# 4-POWER.net
KiCad netlist of a schematic drawn in Altium Designer
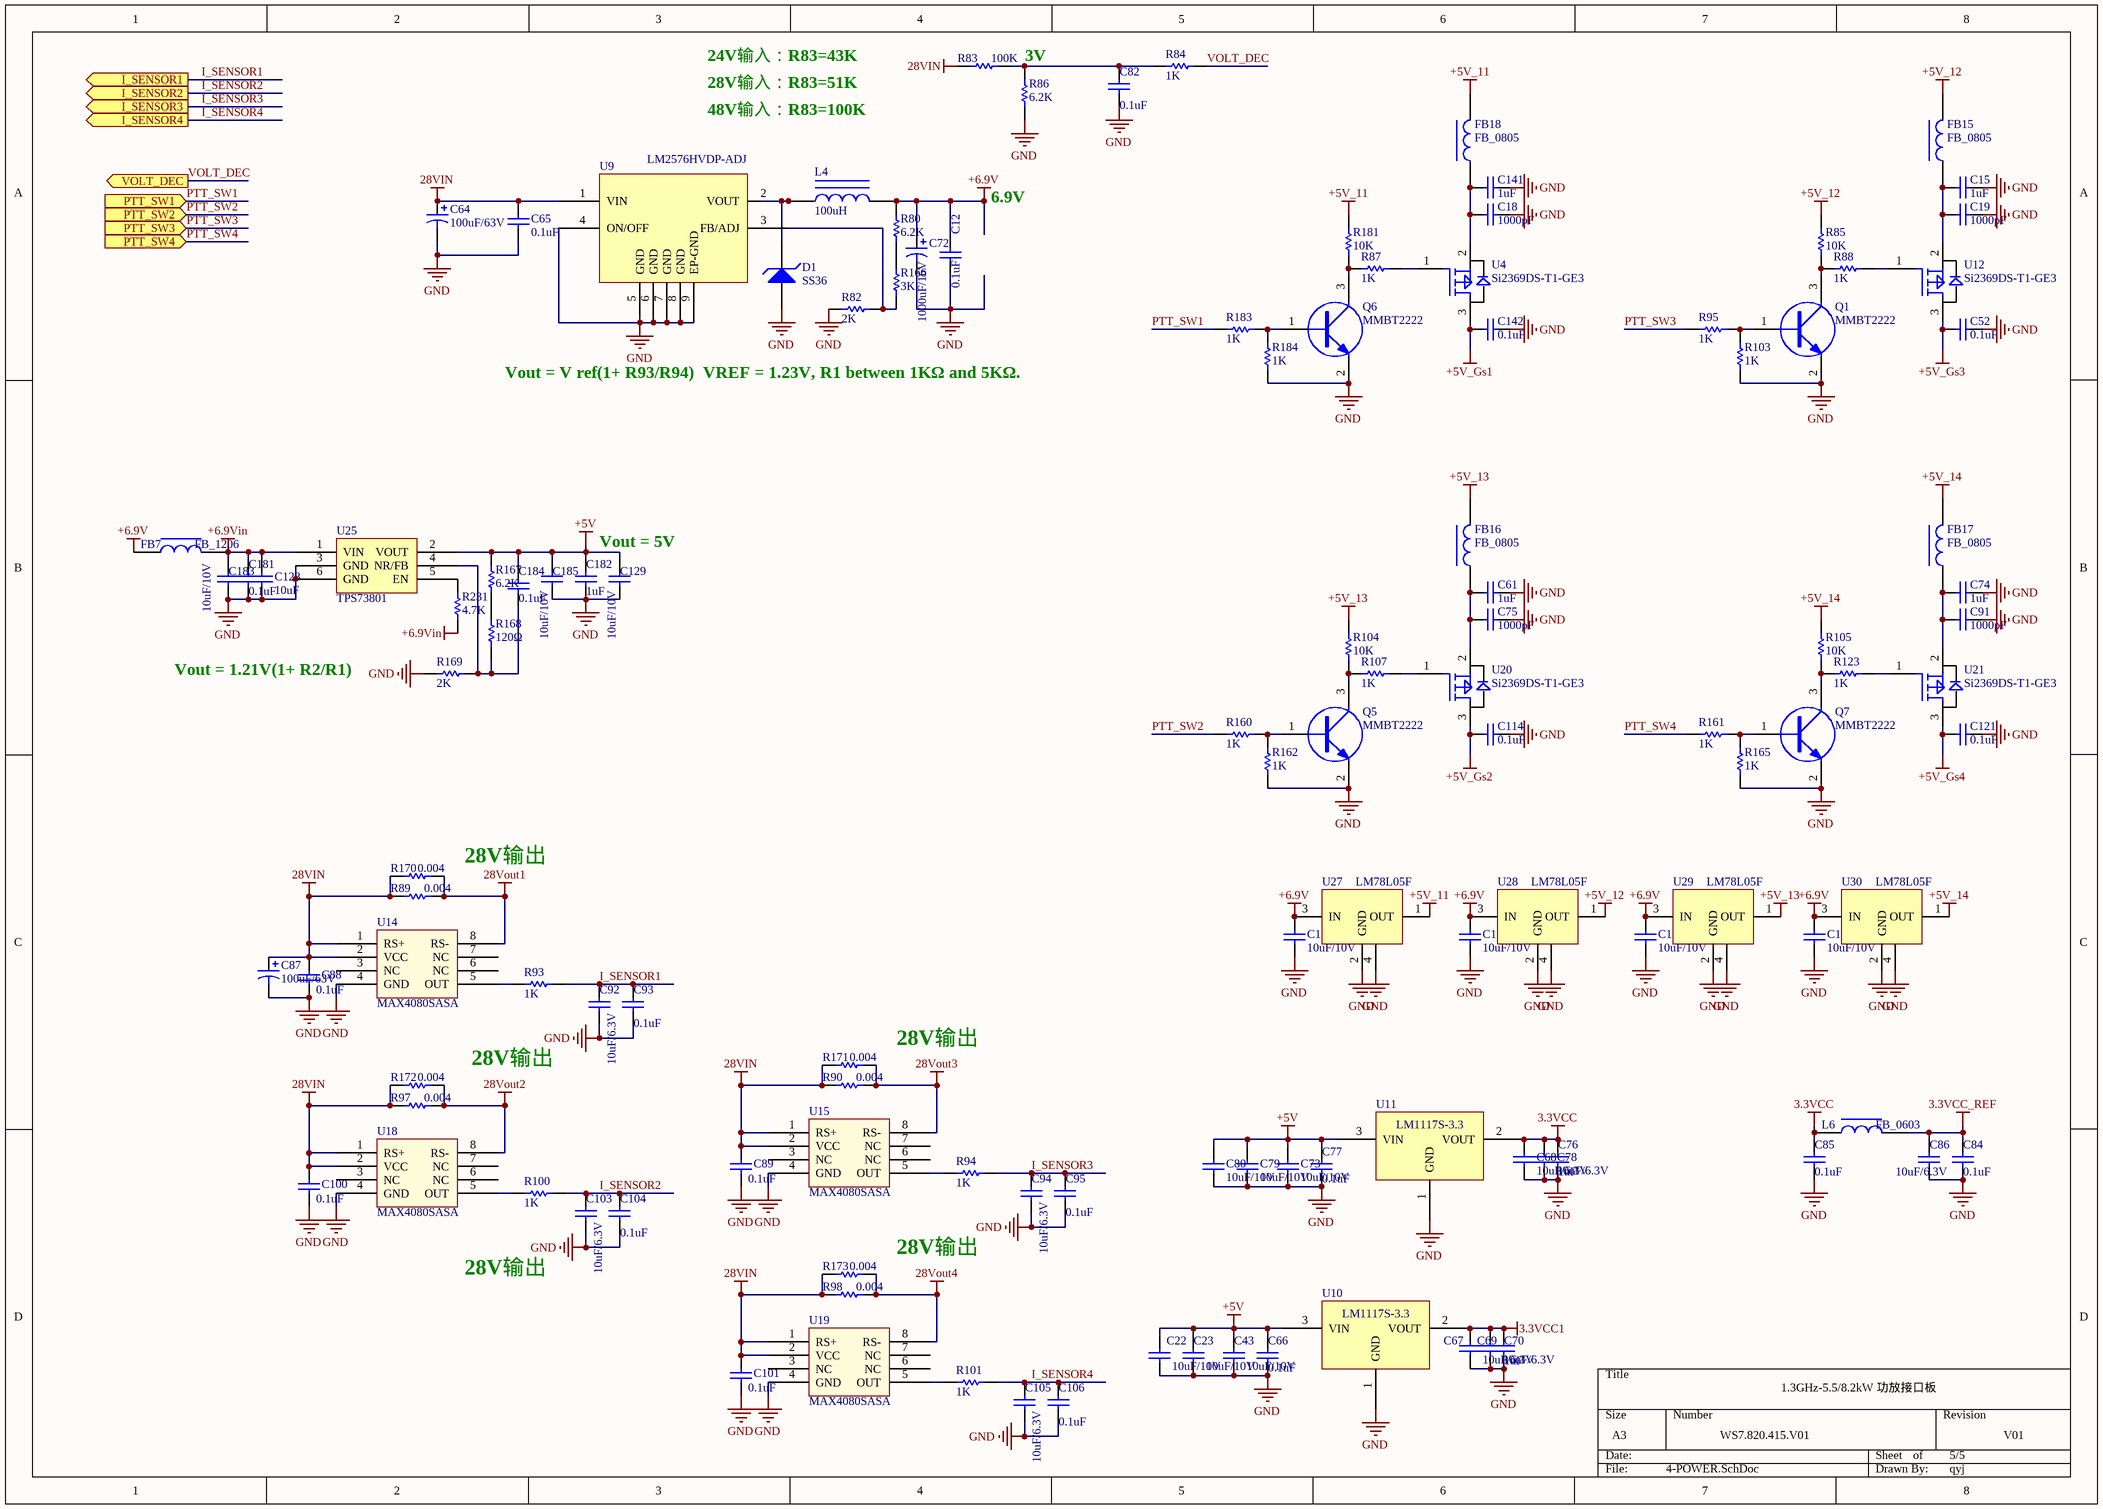
[diagram p0: 4-POWER.SchDoc]

(export (version "E")
  (design (tool "Eeschema 10.0.6"))
  (components
    (comp (ref "C12")
      (value "0.1uF")
      (footprint "C0603")
      (description "贴片电容_GRM188R71H104KA01D_0.1uF±10%,50V,0603")
      (libsource (lib "20贴片电容0603") (part "0.1uF贴片电容"))
    )
    (comp (ref "C15")
      (value "1uF")
      (footprint "C0603")
      (description "贴片电容_GRM188R61A105KA61D_1uF±10%,10V,0603")
      (libsource (lib "20贴片电容0603") (part "1uF贴片电容"))
    )
    (comp (ref "C18")
      (value "1000pF")
      (footprint "C0603")
      (description "贴片电容_GRM188R71H102KA01_1000pF±10%,50V,0603")
      (libsource (lib "20贴片电容0603") (part "1000pF贴片电容"))
    )
    (comp (ref "C19")
      (value "1000pF")
      (footprint "C0603")
      (description "贴片电容_GRM188R71H102KA01_1000pF±10%,50V,0603")
      (libsource (lib "20贴片电容0603") (part "1000pF贴片电容"))
    )
    (comp (ref "C22")
      (value "10uF/10V")
      (footprint "C0805")
      (description "贴片电容_GRM21BR61A106KE19L_10uF±10%,10V,0805")
      (libsource (lib "21贴片电容0805") (part "10uF贴片电容"))
    )
    (comp (ref "C23")
      (value "10uF/10V")
      (footprint "C0805")
      (description "贴片电容_GRM21BR61A106KE19L_10uF±10%,10V,0805")
      (libsource (lib "21贴片电容0805") (part "10uF贴片电容"))
    )
    (comp (ref "C43")
      (value "10uF/10V")
      (footprint "C0805")
      (description "贴片电容_GRM21BR61A106KE19L_10uF±10%,10V,0805")
      (libsource (lib "21贴片电容0805") (part "10uF贴片电容"))
    )
    (comp (ref "C52")
      (value "0.1uF")
      (footprint "C0603")
      (description "贴片电容_GRM188R71H104KA01D_0.1uF±10%,50V,0603")
      (libsource (lib "20贴片电容0603") (part "0.1uF贴片电容"))
    )
    (comp (ref "C61")
      (value "1uF")
      (footprint "C0603")
      (description "贴片电容_GRM188R61A105KA61D_1uF±10%,10V,0603")
      (libsource (lib "20贴片电容0603") (part "1uF贴片电容"))
    )
    (comp (ref "C64")
      (value "100uF/63V")
      (footprint "ECAP2SM_10R4x10R4")
      (description "贴片电解电容_VEJ101M1JTR-1010_100uF/63V,±20%,表贴D10*H10")
      (libsource (lib "24电解电容") (part "100uF/63V"))
    )
    (comp (ref "C65")
      (value "0.1uF")
      (footprint "C0603")
      (description "贴片电容_GRM188R71H104KA01D_0.1uF±10%,50V,0603")
      (libsource (lib "20贴片电容0603") (part "0.1uF贴片电容"))
    )
    (comp (ref "C66")
      (value "0.1uF")
      (footprint "C0603")
      (description "贴片电容_GRM188R71H104KA01D_0.1uF±10%,50V,0603")
      (libsource (lib "20贴片电容0603") (part "0.1uF贴片电容"))
    )
    (comp (ref "C67")
      (value "10uF/6.3V")
      (footprint "C0603")
      (description "贴片电容_GRM188R60J106ME47D_10uF±20%,6.3V,0603")
      (libsource (lib "20贴片电容0603") (part "10uF贴片电容"))
    )
    (comp (ref "C68")
      (value "10uF/6.3V")
      (footprint "C0603")
      (description "贴片电容_GRM188R60J106ME47D_10uF±20%,6.3V,0603")
      (libsource (lib "20贴片电容0603") (part "10uF贴片电容"))
    )
    (comp (ref "C69")
      (value "10uF/6.3V")
      (footprint "C0603")
      (description "贴片电容_GRM188R60J106ME47D_10uF±20%,6.3V,0603")
      (libsource (lib "20贴片电容0603") (part "10uF贴片电容"))
    )
    (comp (ref "C70")
      (value "1uF")
      (footprint "C0603")
      (description "贴片电容_GRM188R61A105KA61D_1uF±10%,10V,0603")
      (libsource (lib "20贴片电容0603") (part "1uF贴片电容"))
    )
    (comp (ref "C72")
      (value "1000uF/16V")
      (footprint "ECAP2SM_10R4x10R4")
      (description "贴片电解电容_VE102M1CTR-1010_1000uF/16V,±20%,表贴10*10")
      (libsource (lib "24电解电容") (part "1000uF/16V"))
    )
    (comp (ref "C73")
      (value "10uF/10V")
      (footprint "C0805")
      (description "贴片电容_GRM21BR61A106KE19L_10uF±10%,10V,0805")
      (libsource (lib "21贴片电容0805") (part "10uF贴片电容"))
    )
    (comp (ref "C74")
      (value "1uF")
      (footprint "C0603")
      (description "贴片电容_GRM188R61A105KA61D_1uF±10%,10V,0603")
      (libsource (lib "20贴片电容0603") (part "1uF贴片电容"))
    )
    (comp (ref "C75")
      (value "1000pF")
      (footprint "C0603")
      (description "贴片电容_GRM188R71H102KA01_1000pF±10%,50V,0603")
      (libsource (lib "20贴片电容0603") (part "1000pF贴片电容"))
    )
    (comp (ref "C76")
      (value "1uF")
      (footprint "C0603")
      (description "贴片电容_GRM188R61A105KA61D_1uF±10%,10V,0603")
      (libsource (lib "20贴片电容0603") (part "1uF贴片电容"))
    )
    (comp (ref "C77")
      (value "0.1uF")
      (footprint "C0603")
      (description "贴片电容_GRM188R71H104KA01D_0.1uF±10%,50V,0603")
      (libsource (lib "20贴片电容0603") (part "0.1uF贴片电容"))
    )
    (comp (ref "C78")
      (value "10uF/6.3V")
      (footprint "C0603")
      (description "贴片电容_GRM188R60J106ME47D_10uF±20%,6.3V,0603")
      (libsource (lib "20贴片电容0603") (part "10uF贴片电容"))
    )
    (comp (ref "C79")
      (value "10uF/10V")
      (footprint "C0805")
      (description "贴片电容_GRM21BR61A106KE19L_10uF±10%,10V,0805")
      (libsource (lib "21贴片电容0805") (part "10uF贴片电容"))
    )
    (comp (ref "C80")
      (value "10uF/10V")
      (footprint "C0805")
      (description "贴片电容_GRM21BR61A106KE19L_10uF±10%,10V,0805")
      (libsource (lib "21贴片电容0805") (part "10uF贴片电容"))
    )
    (comp (ref "C82")
      (value "0.1uF")
      (footprint "C0603")
      (description "贴片电容_GRM188R71H104KA01D_0.1uF±10%,50V,0603")
      (libsource (lib "20贴片电容0603") (part "0.1uF贴片电容"))
    )
    (comp (ref "C84")
      (value "0.1uF")
      (footprint "C0603")
      (description "贴片电容_GRM188R71H104KA01D_0.1uF±10%,50V,0603")
      (libsource (lib "20贴片电容0603") (part "0.1uF贴片电容"))
    )
    (comp (ref "C85")
      (value "0.1uF")
      (footprint "C0603")
      (description "贴片电容_GRM188R71H104KA01D_0.1uF±10%,50V,0603")
      (libsource (lib "20贴片电容0603") (part "0.1uF贴片电容"))
    )
    (comp (ref "C86")
      (value "10uF/6.3V")
      (footprint "C0603")
      (description "贴片电容_GRM188R60J106ME47D_10uF±20%,6.3V,0603")
      (libsource (lib "20贴片电容0603") (part "10uF贴片电容"))
    )
    (comp (ref "C87")
      (value "100uF/63V")
      (footprint "ECAP2SM_10R4x10R4")
      (description "贴片电解电容_VEJ101M1JTR-1010_100uF/63V,±20%,表贴D10*H10")
      (libsource (lib "24电解电容") (part "100uF/63V"))
    )
    (comp (ref "C88")
      (value "0.1uF")
      (footprint "C0603")
      (description "贴片电容_GRM188R71H104KA01D_0.1uF±10%,50V,0603")
      (libsource (lib "20贴片电容0603") (part "0.1uF贴片电容"))
    )
    (comp (ref "C89")
      (value "0.1uF")
      (footprint "C0603")
      (description "贴片电容_GRM188R71H104KA01D_0.1uF±10%,50V,0603")
      (libsource (lib "20贴片电容0603") (part "0.1uF贴片电容"))
    )
    (comp (ref "C91")
      (value "1000pF")
      (footprint "C0603")
      (description "贴片电容_GRM188R71H102KA01_1000pF±10%,50V,0603")
      (libsource (lib "20贴片电容0603") (part "1000pF贴片电容"))
    )
    (comp (ref "C92")
      (value "10uF/6.3V")
      (footprint "C0603")
      (description "贴片电容_GRM188R60J106ME47D_10uF±20%,6.3V,0603")
      (libsource (lib "20贴片电容0603") (part "10uF贴片电容"))
    )
    (comp (ref "C93")
      (value "0.1uF")
      (footprint "C0603")
      (description "贴片电容_GRM188R71H104KA01D_0.1uF±10%,50V,0603")
      (libsource (lib "20贴片电容0603") (part "0.1uF贴片电容"))
    )
    (comp (ref "C94")
      (value "10uF/6.3V")
      (footprint "C0603")
      (description "贴片电容_GRM188R60J106ME47D_10uF±20%,6.3V,0603")
      (libsource (lib "20贴片电容0603") (part "10uF贴片电容"))
    )
    (comp (ref "C95")
      (value "0.1uF")
      (footprint "C0603")
      (description "贴片电容_GRM188R71H104KA01D_0.1uF±10%,50V,0603")
      (libsource (lib "20贴片电容0603") (part "0.1uF贴片电容"))
    )
    (comp (ref "C100")
      (value "0.1uF")
      (footprint "C0603")
      (description "贴片电容_GRM188R71H104KA01D_0.1uF±10%,50V,0603")
      (libsource (lib "20贴片电容0603") (part "0.1uF贴片电容"))
    )
    (comp (ref "C101")
      (value "0.1uF")
      (footprint "C0603")
      (description "贴片电容_GRM188R71H104KA01D_0.1uF±10%,50V,0603")
      (libsource (lib "20贴片电容0603") (part "0.1uF贴片电容"))
    )
    (comp (ref "C103")
      (value "10uF/6.3V")
      (footprint "C0603")
      (description "贴片电容_GRM188R60J106ME47D_10uF±20%,6.3V,0603")
      (libsource (lib "20贴片电容0603") (part "10uF贴片电容"))
    )
    (comp (ref "C104")
      (value "0.1uF")
      (footprint "C0603")
      (description "贴片电容_GRM188R71H104KA01D_0.1uF±10%,50V,0603")
      (libsource (lib "20贴片电容0603") (part "0.1uF贴片电容"))
    )
    (comp (ref "C105")
      (value "10uF/6.3V")
      (footprint "C0603")
      (description "贴片电容_GRM188R60J106ME47D_10uF±20%,6.3V,0603")
      (libsource (lib "20贴片电容0603") (part "10uF贴片电容"))
    )
    (comp (ref "C106")
      (value "0.1uF")
      (footprint "C0603")
      (description "贴片电容_GRM188R71H104KA01D_0.1uF±10%,50V,0603")
      (libsource (lib "20贴片电容0603") (part "0.1uF贴片电容"))
    )
    (comp (ref "C114")
      (value "0.1uF")
      (footprint "C0603")
      (description "贴片电容_GRM188R71H104KA01D_0.1uF±10%,50V,0603")
      (libsource (lib "20贴片电容0603") (part "0.1uF贴片电容"))
    )
    (comp (ref "C121")
      (value "0.1uF")
      (footprint "C0603")
      (description "贴片电容_GRM188R71H104KA01D_0.1uF±10%,50V,0603")
      (libsource (lib "20贴片电容0603") (part "0.1uF贴片电容"))
    )
    (comp (ref "C128")
      (value "10uF")
      (footprint "C1210")
      (description "贴片电容_GRM32ER71H106KA12L_10uF±10%,50V,1210")
      (libsource (lib "23贴片电容1210") (part "10uF贴片电容"))
    )
    (comp (ref "C129")
      (value "10uF/10V")
      (footprint "C0805")
      (description "贴片电容_GRM21BR61A106KE19L_10uF±10%,10V,0805")
      (libsource (lib "21贴片电容0805") (part "10uF贴片电容"))
    )
    (comp (ref "C132")
      (value "10uF/10V")
      (footprint "C0805")
      (description "贴片电容_GRM21BR61A106KE19L_10uF±10%,10V,0805")
      (libsource (lib "21贴片电容0805") (part "10uF贴片电容"))
    )
    (comp (ref "C133")
      (value "10uF/10V")
      (footprint "C0805")
      (description "贴片电容_GRM21BR61A106KE19L_10uF±10%,10V,0805")
      (libsource (lib "21贴片电容0805") (part "10uF贴片电容"))
    )
    (comp (ref "C134")
      (value "10uF/10V")
      (footprint "C0805")
      (description "贴片电容_GRM21BR61A106KE19L_10uF±10%,10V,0805")
      (libsource (lib "21贴片电容0805") (part "10uF贴片电容"))
    )
    (comp (ref "C135")
      (value "10uF/10V")
      (footprint "C0805")
      (description "贴片电容_GRM21BR61A106KE19L_10uF±10%,10V,0805")
      (libsource (lib "21贴片电容0805") (part "10uF贴片电容"))
    )
    (comp (ref "C141")
      (value "1uF")
      (footprint "C0603")
      (description "贴片电容_GRM188R61A105KA61D_1uF±10%,10V,0603")
      (libsource (lib "20贴片电容0603") (part "1uF贴片电容"))
    )
    (comp (ref "C142")
      (value "0.1uF")
      (footprint "C0603")
      (description "贴片电容_GRM188R71H104KA01D_0.1uF±10%,50V,0603")
      (libsource (lib "20贴片电容0603") (part "0.1uF贴片电容"))
    )
    (comp (ref "C181")
      (value "0.1uF")
      (footprint "C0603")
      (description "贴片电容_GRM188R71H104KA01D_0.1uF±10%,50V,0603")
      (libsource (lib "20贴片电容0603") (part "0.1uF贴片电容"))
    )
    (comp (ref "C182")
      (value "1uF")
      (footprint "C0603")
      (description "贴片电容_GRM188R61A105KA61D_1uF±10%,10V,0603")
      (libsource (lib "20贴片电容0603") (part "1uF贴片电容"))
    )
    (comp (ref "C183")
      (value "10uF/10V")
      (footprint "C0805")
      (description "贴片电容_GRM21BR61A106KE19L_10uF±10%,10V,0805")
      (libsource (lib "21贴片电容0805") (part "10uF贴片电容"))
    )
    (comp (ref "C184")
      (value "0.1uF")
      (footprint "C0603")
      (description "贴片电容_GRM188R71H104KA01D_0.1uF±10%,50V,0603")
      (libsource (lib "20贴片电容0603") (part "0.1uF贴片电容"))
    )
    (comp (ref "C185")
      (value "10uF/10V")
      (footprint "C0805")
      (description "贴片电容_GRM21BR61A106KE19L_10uF±10%,10V,0805")
      (libsource (lib "21贴片电容0805") (part "10uF贴片电容"))
    )
    (comp (ref "D1")
      (value "SS36")
      (footprint "DO-214AC")
      (description "肖特基整流二极管_SS36_封装SMA,3A/60V")
      (libsource (lib "40二极管") (part "肖特基整流二极管_SS36"))
    )
    (comp (ref "FB7")
      (value "FB_1206")
      (footprint "L1206")
      (description "贴片磁珠_30R,6A,1206")
      (libsource (lib "34贴片磁珠1206") (part "1206贴片磁珠"))
    )
    (comp (ref "FB15")
      (value "FB_0805")
      (footprint "L0805")
      (description "贴片磁珠_600R,0805")
      (libsource (lib "33贴片磁珠0805") (part "0805贴片磁珠"))
    )
    (comp (ref "FB16")
      (value "FB_0805")
      (footprint "L0805")
      (description "贴片磁珠_600R,0805")
      (libsource (lib "33贴片磁珠0805") (part "0805贴片磁珠"))
    )
    (comp (ref "FB17")
      (value "FB_0805")
      (footprint "L0805")
      (description "贴片磁珠_600R,0805")
      (libsource (lib "33贴片磁珠0805") (part "0805贴片磁珠"))
    )
    (comp (ref "FB18")
      (value "FB_0805")
      (footprint "L0805")
      (description "贴片磁珠_600R,0805")
      (libsource (lib "33贴片磁珠0805") (part "0805贴片磁珠"))
    )
    (comp (ref "L4")
      (value "100uH")
      (footprint "PL2SM-12R5x12R5")
      (description "贴片功率电感_SLF12575T-101M1R9-PF_100uH±20%,额定电流1.9A,12.5x12.5")
      (libsource (lib "32贴片功率电感") (part "100uH贴片功率电感"))
    )
    (comp (ref "L6")
      (value "FB_0603")
      (footprint "L0603")
      (description "贴片磁珠_100R,0603")
      (libsource (lib "32贴片磁珠0603") (part "0603贴片磁珠"))
    )
    (comp (ref "Q1")
      (value "MMBT2222")
      (footprint "SOT23-3")
      (description "NPN三极管_MMBT2222_表贴SOT23")
      (libsource (lib "50三极管") (part "MMBT2222"))
    )
    (comp (ref "Q5")
      (value "MMBT2222")
      (footprint "SOT23-3")
      (description "NPN三极管_MMBT2222_表贴SOT23")
      (libsource (lib "50三极管") (part "MMBT2222"))
    )
    (comp (ref "Q6")
      (value "MMBT2222")
      (footprint "SOT23-3")
      (description "NPN三极管_MMBT2222_表贴SOT23")
      (libsource (lib "50三极管") (part "MMBT2222"))
    )
    (comp (ref "Q7")
      (value "MMBT2222")
      (footprint "SOT23-3")
      (description "NPN三极管_MMBT2222_表贴SOT23")
      (libsource (lib "50三极管") (part "MMBT2222"))
    )
    (comp (ref "R80")
      (value "6.2K")
      (footprint "R0603")
      (description "贴片电阻_6.2K±5%,0603")
      (libsource (lib "10贴片电阻0603") (part "6.2K贴片电阻"))
    )
    (comp (ref "R82")
      (value "2K")
      (footprint "R0603")
      (description "贴片电阻_2K±5%,0603")
      (libsource (lib "10贴片电阻0603") (part "2K贴片电阻"))
    )
    (comp (ref "R83")
      (value "100K")
      (footprint "R0603")
      (description "贴片电阻_12.4K±1%,0603")
      (libsource (lib "10贴片电阻0603") (part "12.4K贴片电阻"))
    )
    (comp (ref "R84")
      (value "1K")
      (footprint "R0603")
      (description "贴片电阻_1K±5%,0603")
      (libsource (lib "10贴片电阻0603") (part "1K贴片电阻"))
    )
    (comp (ref "R85")
      (value "10K")
      (footprint "R0603")
      (description "贴片电阻_10K±5%,0603")
      (libsource (lib "10贴片电阻0603") (part "10K贴片电阻"))
    )
    (comp (ref "R86")
      (value "6.2K")
      (footprint "R0603")
      (description "贴片电阻_1.5K±5%,0603")
      (libsource (lib "10贴片电阻0603") (part "1.5K贴片电阻"))
    )
    (comp (ref "R87")
      (value "1K")
      (footprint "R0603")
      (description "贴片电阻_1K±5%,0603")
      (libsource (lib "10贴片电阻0603") (part "1K贴片电阻"))
    )
    (comp (ref "R88")
      (value "1K")
      (footprint "R0603")
      (description "贴片电阻_1K±5%,0603")
      (libsource (lib "10贴片电阻0603") (part "1K贴片电阻"))
    )
    (comp (ref "R89")
      (value "0.004")
      (footprint "R2512")
      (description "贴片电阻_LR12DTDSR004_0.004±5%,2W,2512")
      (libsource (lib "15贴片检流电阻") (part "0.004Ω检流电阻-标准封装"))
    )
    (comp (ref "R90")
      (value "0.004")
      (footprint "R2512")
      (description "贴片电阻_LR12DTDSR004_0.004±5%,2W,2512")
      (libsource (lib "15贴片检流电阻") (part "0.004Ω检流电阻-标准封装"))
    )
    (comp (ref "R93")
      (value "1K")
      (footprint "R0603")
      (description "贴片电阻_1K±5%,0603")
      (libsource (lib "10贴片电阻0603") (part "1K贴片电阻"))
    )
    (comp (ref "R94")
      (value "1K")
      (footprint "R0603")
      (description "贴片电阻_1K±5%,0603")
      (libsource (lib "10贴片电阻0603") (part "1K贴片电阻"))
    )
    (comp (ref "R95")
      (value "1K")
      (footprint "R0603")
      (description "贴片电阻_1K±5%,0603")
      (libsource (lib "10贴片电阻0603") (part "1K贴片电阻"))
    )
    (comp (ref "R97")
      (value "0.004")
      (footprint "R2512")
      (description "贴片电阻_LR12DTDSR004_0.004±5%,2W,2512")
      (libsource (lib "15贴片检流电阻") (part "0.004Ω检流电阻-标准封装"))
    )
    (comp (ref "R98")
      (value "0.004")
      (footprint "R2512")
      (description "贴片电阻_LR12DTDSR004_0.004±5%,2W,2512")
      (libsource (lib "15贴片检流电阻") (part "0.004Ω检流电阻-标准封装"))
    )
    (comp (ref "R100")
      (value "1K")
      (footprint "R0603")
      (description "贴片电阻_1K±5%,0603")
      (libsource (lib "10贴片电阻0603") (part "1K贴片电阻"))
    )
    (comp (ref "R101")
      (value "1K")
      (footprint "R0603")
      (description "贴片电阻_1K±5%,0603")
      (libsource (lib "10贴片电阻0603") (part "1K贴片电阻"))
    )
    (comp (ref "R103")
      (value "1K")
      (footprint "R0603")
      (description "贴片电阻_1K±5%,0603")
      (libsource (lib "10贴片电阻0603") (part "1K贴片电阻"))
    )
    (comp (ref "R104")
      (value "10K")
      (footprint "R0603")
      (description "贴片电阻_10K±5%,0603")
      (libsource (lib "10贴片电阻0603") (part "10K贴片电阻"))
    )
    (comp (ref "R105")
      (value "10K")
      (footprint "R0603")
      (description "贴片电阻_10K±5%,0603")
      (libsource (lib "10贴片电阻0603") (part "10K贴片电阻"))
    )
    (comp (ref "R107")
      (value "1K")
      (footprint "R0603")
      (description "贴片电阻_1K±5%,0603")
      (libsource (lib "10贴片电阻0603") (part "1K贴片电阻"))
    )
    (comp (ref "R123")
      (value "1K")
      (footprint "R0603")
      (description "贴片电阻_1K±5%,0603")
      (libsource (lib "10贴片电阻0603") (part "1K贴片电阻"))
    )
    (comp (ref "R160")
      (value "1K")
      (footprint "R0603")
      (description "贴片电阻_1K±5%,0603")
      (libsource (lib "10贴片电阻0603") (part "1K贴片电阻"))
    )
    (comp (ref "R161")
      (value "1K")
      (footprint "R0603")
      (description "贴片电阻_1K±5%,0603")
      (libsource (lib "10贴片电阻0603") (part "1K贴片电阻"))
    )
    (comp (ref "R162")
      (value "1K")
      (footprint "R0603")
      (description "贴片电阻_1K±5%,0603")
      (libsource (lib "10贴片电阻0603") (part "1K贴片电阻"))
    )
    (comp (ref "R165")
      (value "1K")
      (footprint "R0603")
      (description "贴片电阻_1K±5%,0603")
      (libsource (lib "10贴片电阻0603") (part "1K贴片电阻"))
    )
    (comp (ref "R166")
      (value "3K")
      (footprint "R0603")
      (description "贴片电阻_3K±5%,0603")
      (libsource (lib "10贴片电阻0603") (part "3K贴片电阻"))
    )
    (comp (ref "R167")
      (value "6.2K")
      (footprint "R0603")
      (description "贴片电阻_6.2K±5%,0603")
      (libsource (lib "10贴片电阻0603") (part "6.2K贴片电阻"))
    )
    (comp (ref "R168")
      (value "120Ω")
      (footprint "R0603")
      (description "贴片电阻_120Ω±5%,0603")
      (libsource (lib "10贴片电阻0603") (part "120Ω贴片电阻"))
    )
    (comp (ref "R169")
      (value "2K")
      (footprint "R0603")
      (description "贴片电阻_2K±5%,0603")
      (libsource (lib "10贴片电阻0603") (part "2K贴片电阻"))
    )
    (comp (ref "R170")
      (value "0.004")
      (footprint "R2512")
      (description "贴片电阻_LR12DTDSR004_0.004±5%,2W,2512")
      (libsource (lib "15贴片检流电阻") (part "0.004Ω检流电阻-标准封装"))
    )
    (comp (ref "R171")
      (value "0.004")
      (footprint "R2512")
      (description "贴片电阻_LR12DTDSR004_0.004±5%,2W,2512")
      (libsource (lib "15贴片检流电阻") (part "0.004Ω检流电阻-标准封装"))
    )
    (comp (ref "R172")
      (value "0.004")
      (footprint "R2512")
      (description "贴片电阻_LR12DTDSR004_0.004±5%,2W,2512")
      (libsource (lib "15贴片检流电阻") (part "0.004Ω检流电阻-标准封装"))
    )
    (comp (ref "R173")
      (value "0.004")
      (footprint "R2512")
      (description "贴片电阻_LR12DTDSR004_0.004±5%,2W,2512")
      (libsource (lib "15贴片检流电阻") (part "0.004Ω检流电阻-标准封装"))
    )
    (comp (ref "R181")
      (value "10K")
      (footprint "R0603")
      (description "贴片电阻_10K±5%,0603")
      (libsource (lib "10贴片电阻0603") (part "10K贴片电阻"))
    )
    (comp (ref "R183")
      (value "1K")
      (footprint "R0603")
      (description "贴片电阻_1K±5%,0603")
      (libsource (lib "10贴片电阻0603") (part "1K贴片电阻"))
    )
    (comp (ref "R184")
      (value "1K")
      (footprint "R0603")
      (description "贴片电阻_1K±5%,0603")
      (libsource (lib "10贴片电阻0603") (part "1K贴片电阻"))
    )
    (comp (ref "R231")
      (value "4.7K")
      (footprint "R0603")
      (description "贴片电阻_4.7K±5%,0603")
      (libsource (lib "10贴片电阻0603") (part "4.7K贴片电阻"))
    )
    (comp (ref "U4")
      (value "Si2369DS-T1-GE3")
      (footprint "SOT23-3")
      (description "P-MOS_Si2369DS-T1-GE3_SOT23")
      (libsource (lib "51场效应管") (part "Si2369DS-T1-GE3"))
    )
    (comp (ref "U9")
      (value "LM2576HVDP-ADJ")
      (footprint "SOIC8_1R27_3R9x4R9-1")
      (description "稳压集成电路_LM2576HVDP-ADJ_3A输出,SOIC8")
      (libsource (lib "78电源芯片") (part "LM2576HVDP-ADJ"))
    )
    (comp (ref "U10")
      (value "LM1117S-3.3")
      (footprint "SOT-223")
      (description "LDO_LM1117S-3.3_1A输出,SOT223")
      (libsource (lib "78电源芯片") (part "LM1117S-3.3"))
    )
    (comp (ref "U11")
      (value "LM1117S-3.3")
      (footprint "SOT-223")
      (description "LDO_LM1117S-3.3_1A输出,SOT223")
      (libsource (lib "78电源芯片") (part "LM1117S-3.3"))
    )
    (comp (ref "U12")
      (value "Si2369DS-T1-GE3")
      (footprint "SOT23-3")
      (description "P-MOS_Si2369DS-T1-GE3_SOT23")
      (libsource (lib "51场效应管") (part "Si2369DS-T1-GE3"))
    )
    (comp (ref "U14")
      (value "MAX4080SASA")
      (footprint "SOIC8_1R27_3R9x4R9")
      (description "电流检测放大器_MAX4080SASA_SOIC8")
      (libsource (lib "79电流检测芯片") (part "MAX4080TASA"))
    )
    (comp (ref "U15")
      (value "MAX4080SASA")
      (footprint "SOIC8_1R27_3R9x4R9")
      (description "电流检测放大器_MAX4080SASA_SOIC8")
      (libsource (lib "79电流检测芯片") (part "MAX4080TASA"))
    )
    (comp (ref "U18")
      (value "MAX4080SASA")
      (footprint "SOIC8_1R27_3R9x4R9")
      (description "电流检测放大器_MAX4080SASA_SOIC8")
      (libsource (lib "79电流检测芯片") (part "MAX4080TASA"))
    )
    (comp (ref "U19")
      (value "MAX4080SASA")
      (footprint "SOIC8_1R27_3R9x4R9")
      (description "电流检测放大器_MAX4080SASA_SOIC8")
      (libsource (lib "79电流检测芯片") (part "MAX4080TASA"))
    )
    (comp (ref "U20")
      (value "Si2369DS-T1-GE3")
      (footprint "SOT23-3")
      (description "P-MOS_Si2369DS-T1-GE3_SOT23")
      (libsource (lib "51场效应管") (part "Si2369DS-T1-GE3"))
    )
    (comp (ref "U21")
      (value "Si2369DS-T1-GE3")
      (footprint "SOT23-3")
      (description "P-MOS_Si2369DS-T1-GE3_SOT23")
      (libsource (lib "51场效应管") (part "Si2369DS-T1-GE3"))
    )
    (comp (ref "U25")
      (value "TPS73801")
      (footprint "SOT-223-6")
      (description "LDO_TPS73801_1A输出,SOT223-6")
      (libsource (lib "78电源芯片") (part "TPS73701DCQ"))
    )
    (comp (ref "U27")
      (value "LM78L05F")
      (footprint "SOT-89")
      (description "功率放大器_LM78L05F_5V输出,100mA输出,SOT89")
      (libsource (lib "78电源芯片") (part "LM78L05F"))
    )
    (comp (ref "U28")
      (value "LM78L05F")
      (footprint "SOT-89")
      (description "功率放大器_LM78L05F_5V输出,100mA输出,SOT89")
      (libsource (lib "78电源芯片") (part "LM78L05F"))
    )
    (comp (ref "U29")
      (value "LM78L05F")
      (footprint "SOT-89")
      (description "功率放大器_LM78L05F_5V输出,100mA输出,SOT89")
      (libsource (lib "78电源芯片") (part "LM78L05F"))
    )
    (comp (ref "U30")
      (value "LM78L05F")
      (footprint "SOT-89")
      (description "功率放大器_LM78L05F_5V输出,100mA输出,SOT89")
      (libsource (lib "78电源芯片") (part "LM78L05F"))
    )
  )
  (nets
    (net (code "1") (name "+5V") (class "Default")
      (node (ref "C129") (pin "2") (pinfunction "2_2") (pintype "passive"))
      (node (ref "C182") (pin "2") (pinfunction "2_2") (pintype "passive"))
      (node (ref "C184") (pin "2") (pinfunction "2_2") (pintype "passive"))
      (node (ref "C185") (pin "2") (pinfunction "2_2") (pintype "passive"))
      (node (ref "C22") (pin "2") (pinfunction "2_2") (pintype "passive"))
      (node (ref "C23") (pin "2") (pinfunction "2_2") (pintype "passive"))
      (node (ref "C43") (pin "2") (pinfunction "2_2") (pintype "passive"))
      (node (ref "C66") (pin "2") (pinfunction "2_2") (pintype "passive"))
      (node (ref "C73") (pin "2") (pinfunction "2_2") (pintype "passive"))
      (node (ref "C77") (pin "2") (pinfunction "2_2") (pintype "passive"))
      (node (ref "C79") (pin "2") (pinfunction "2_2") (pintype "passive"))
      (node (ref "C80") (pin "2") (pinfunction "2_2") (pintype "passive"))
      (node (ref "R167") (pin "2") (pinfunction "2_2") (pintype "passive"))
      (node (ref "U10") (pin "3") (pinfunction "VIN_3") (pintype "passive"))
      (node (ref "U11") (pin "3") (pinfunction "VIN_3") (pintype "passive"))
      (node (ref "U25") (pin "2") (pinfunction "VOUT_2") (pintype "passive"))
    )
    (net (code "2") (name "+5V_11") (class "Default")
      (node (ref "FB18") (pin "2") (pinfunction "2_2") (pintype "passive"))
      (node (ref "R181") (pin "2") (pinfunction "2_2") (pintype "passive"))
      (node (ref "U27") (pin "1") (pinfunction "OUT_1") (pintype "passive"))
    )
    (net (code "3") (name "+5V_12") (class "Default")
      (node (ref "FB15") (pin "2") (pinfunction "2_2") (pintype "passive"))
      (node (ref "R85") (pin "2") (pinfunction "2_2") (pintype "passive"))
      (node (ref "U28") (pin "1") (pinfunction "OUT_1") (pintype "passive"))
    )
    (net (code "4") (name "+5V_13") (class "Default")
      (node (ref "FB16") (pin "2") (pinfunction "2_2") (pintype "passive"))
      (node (ref "R104") (pin "2") (pinfunction "2_2") (pintype "passive"))
      (node (ref "U29") (pin "1") (pinfunction "OUT_1") (pintype "passive"))
    )
    (net (code "5") (name "+5V_14") (class "Default")
      (node (ref "FB17") (pin "2") (pinfunction "2_2") (pintype "passive"))
      (node (ref "R105") (pin "2") (pinfunction "2_2") (pintype "passive"))
      (node (ref "U30") (pin "1") (pinfunction "OUT_1") (pintype "passive"))
    )
    (net (code "6") (name "+5V_Gs1") (class "Default")
      (node (ref "C142") (pin "2") (pinfunction "2_2") (pintype "passive"))
      (node (ref "U4") (pin "3") (pinfunction "D_3") (pintype "passive"))
    )
    (net (code "7") (name "+5V_Gs2") (class "Default")
      (node (ref "C114") (pin "2") (pinfunction "2_2") (pintype "passive"))
      (node (ref "U20") (pin "3") (pinfunction "D_3") (pintype "passive"))
    )
    (net (code "8") (name "+5V_Gs3") (class "Default")
      (node (ref "C52") (pin "2") (pinfunction "2_2") (pintype "passive"))
      (node (ref "U12") (pin "3") (pinfunction "D_3") (pintype "passive"))
    )
    (net (code "9") (name "+5V_Gs4") (class "Default")
      (node (ref "C121") (pin "2") (pinfunction "2_2") (pintype "passive"))
      (node (ref "U21") (pin "3") (pinfunction "D_3") (pintype "passive"))
    )
    (net (code "10") (name "+6.9V") (class "Default")
      (node (ref "C12") (pin "2") (pinfunction "2_2") (pintype "passive"))
      (node (ref "C132") (pin "2") (pinfunction "2_2") (pintype "passive"))
      (node (ref "C133") (pin "2") (pinfunction "2_2") (pintype "passive"))
      (node (ref "C134") (pin "2") (pinfunction "2_2") (pintype "passive"))
      (node (ref "C135") (pin "2") (pinfunction "2_2") (pintype "passive"))
      (node (ref "C72") (pin "1") (pinfunction "1_1") (pintype "passive"))
      (node (ref "FB7") (pin "1") (pinfunction "1_1") (pintype "passive"))
      (node (ref "L4") (pin "2") (pinfunction "2_2") (pintype "passive"))
      (node (ref "R80") (pin "2") (pinfunction "2_2") (pintype "passive"))
      (node (ref "U27") (pin "3") (pinfunction "IN_3") (pintype "passive"))
      (node (ref "U28") (pin "3") (pinfunction "IN_3") (pintype "passive"))
      (node (ref "U29") (pin "3") (pinfunction "IN_3") (pintype "passive"))
      (node (ref "U30") (pin "3") (pinfunction "IN_3") (pintype "passive"))
    )
    (net (code "11") (name "+6.9Vin") (class "Default")
      (node (ref "C128") (pin "2") (pinfunction "2_2") (pintype "passive"))
      (node (ref "C181") (pin "2") (pinfunction "2_2") (pintype "passive"))
      (node (ref "C183") (pin "2") (pinfunction "2_2") (pintype "passive"))
      (node (ref "FB7") (pin "2") (pinfunction "2_2") (pintype "passive"))
      (node (ref "R231") (pin "2") (pinfunction "2_2") (pintype "passive"))
      (node (ref "U25") (pin "1") (pinfunction "VIN_1") (pintype "passive"))
    )
    (net (code "12") (name "/I_SENSOR1") (class "Default")
      (node (ref "C92") (pin "2") (pinfunction "2_2") (pintype "passive"))
      (node (ref "C93") (pin "2") (pinfunction "2_2") (pintype "passive"))
      (node (ref "R93") (pin "2") (pinfunction "2_2") (pintype "passive"))
    )
    (net (code "13") (name "/I_SENSOR2") (class "Default")
      (node (ref "C103") (pin "2") (pinfunction "2_2") (pintype "passive"))
      (node (ref "C104") (pin "2") (pinfunction "2_2") (pintype "passive"))
      (node (ref "R100") (pin "2") (pinfunction "2_2") (pintype "passive"))
    )
    (net (code "14") (name "/I_SENSOR3") (class "Default")
      (node (ref "C94") (pin "2") (pinfunction "2_2") (pintype "passive"))
      (node (ref "C95") (pin "2") (pinfunction "2_2") (pintype "passive"))
      (node (ref "R94") (pin "2") (pinfunction "2_2") (pintype "passive"))
    )
    (net (code "15") (name "/I_SENSOR4") (class "Default")
      (node (ref "C105") (pin "2") (pinfunction "2_2") (pintype "passive"))
      (node (ref "C106") (pin "2") (pinfunction "2_2") (pintype "passive"))
      (node (ref "R101") (pin "2") (pinfunction "2_2") (pintype "passive"))
    )
    (net (code "16") (name "/PTT_SW1") (class "Default")
      (node (ref "R183") (pin "1") (pinfunction "1_1") (pintype "passive"))
    )
    (net (code "17") (name "/PTT_SW2") (class "Default")
      (node (ref "R160") (pin "1") (pinfunction "1_1") (pintype "passive"))
    )
    (net (code "18") (name "/PTT_SW3") (class "Default")
      (node (ref "R95") (pin "1") (pinfunction "1_1") (pintype "passive"))
    )
    (net (code "19") (name "/PTT_SW4") (class "Default")
      (node (ref "R161") (pin "1") (pinfunction "1_1") (pintype "passive"))
    )
    (net (code "20") (name "/VOLT_DEC") (class "Default")
      (node (ref "R84") (pin "1") (pinfunction "1_1") (pintype "passive"))
    )
    (net (code "21") (name "3.3VCC") (class "Default")
      (node (ref "C68") (pin "2") (pinfunction "2_2") (pintype "passive"))
      (node (ref "C76") (pin "2") (pinfunction "2_2") (pintype "passive"))
      (node (ref "C78") (pin "2") (pinfunction "2_2") (pintype "passive"))
      (node (ref "C85") (pin "2") (pinfunction "2_2") (pintype "passive"))
      (node (ref "L6") (pin "1") (pinfunction "1_1") (pintype "passive"))
      (node (ref "U11") (pin "2") (pinfunction "VOUT_2") (pintype "passive"))
    )
    (net (code "22") (name "3.3VCC1") (class "Default")
      (node (ref "C67") (pin "2") (pinfunction "2_2") (pintype "passive"))
      (node (ref "C69") (pin "2") (pinfunction "2_2") (pintype "passive"))
      (node (ref "C70") (pin "2") (pinfunction "2_2") (pintype "passive"))
      (node (ref "U10") (pin "2") (pinfunction "VOUT_2") (pintype "passive"))
    )
    (net (code "23") (name "3.3VCC_REF") (class "Default")
      (node (ref "C84") (pin "2") (pinfunction "2_2") (pintype "passive"))
      (node (ref "C86") (pin "2") (pinfunction "2_2") (pintype "passive"))
      (node (ref "L6") (pin "2") (pinfunction "2_2") (pintype "passive"))
    )
    (net (code "24") (name "28VIN") (class "Default")
      (node (ref "C100") (pin "2") (pinfunction "2_2") (pintype "passive"))
      (node (ref "C101") (pin "2") (pinfunction "2_2") (pintype "passive"))
      (node (ref "C64") (pin "1") (pinfunction "1_1") (pintype "passive"))
      (node (ref "C65") (pin "2") (pinfunction "2_2") (pintype "passive"))
      (node (ref "C87") (pin "1") (pinfunction "1_1") (pintype "passive"))
      (node (ref "C88") (pin "2") (pinfunction "2_2") (pintype "passive"))
      (node (ref "C89") (pin "2") (pinfunction "2_2") (pintype "passive"))
      (node (ref "R170") (pin "1") (pinfunction "1_1") (pintype "passive"))
      (node (ref "R171") (pin "1") (pinfunction "1_1") (pintype "passive"))
      (node (ref "R172") (pin "1") (pinfunction "1_1") (pintype "passive"))
      (node (ref "R173") (pin "1") (pinfunction "1_1") (pintype "passive"))
      (node (ref "R83") (pin "1") (pinfunction "1_1") (pintype "passive"))
      (node (ref "R89") (pin "1") (pinfunction "1_1") (pintype "passive"))
      (node (ref "R90") (pin "1") (pinfunction "1_1") (pintype "passive"))
      (node (ref "R97") (pin "1") (pinfunction "1_1") (pintype "passive"))
      (node (ref "R98") (pin "1") (pinfunction "1_1") (pintype "passive"))
      (node (ref "U14") (pin "1") (pinfunction "RS+_1") (pintype "passive"))
      (node (ref "U14") (pin "2") (pinfunction "VCC_2") (pintype "passive"))
      (node (ref "U15") (pin "1") (pinfunction "RS+_1") (pintype "passive"))
      (node (ref "U15") (pin "2") (pinfunction "VCC_2") (pintype "passive"))
      (node (ref "U18") (pin "1") (pinfunction "RS+_1") (pintype "passive"))
      (node (ref "U18") (pin "2") (pinfunction "VCC_2") (pintype "passive"))
      (node (ref "U19") (pin "1") (pinfunction "RS+_1") (pintype "passive"))
      (node (ref "U19") (pin "2") (pinfunction "VCC_2") (pintype "passive"))
      (node (ref "U9") (pin "1") (pinfunction "VIN_1") (pintype "passive"))
    )
    (net (code "25") (name "28Vout1") (class "Default")
      (node (ref "R170") (pin "2") (pinfunction "2_2") (pintype "passive"))
      (node (ref "R89") (pin "2") (pinfunction "2_2") (pintype "passive"))
      (node (ref "U14") (pin "8") (pinfunction "RS-_8") (pintype "passive"))
    )
    (net (code "26") (name "28Vout2") (class "Default")
      (node (ref "R172") (pin "2") (pinfunction "2_2") (pintype "passive"))
      (node (ref "R97") (pin "2") (pinfunction "2_2") (pintype "passive"))
      (node (ref "U18") (pin "8") (pinfunction "RS-_8") (pintype "passive"))
    )
    (net (code "27") (name "28Vout3") (class "Default")
      (node (ref "R171") (pin "2") (pinfunction "2_2") (pintype "passive"))
      (node (ref "R90") (pin "2") (pinfunction "2_2") (pintype "passive"))
      (node (ref "U15") (pin "8") (pinfunction "RS-_8") (pintype "passive"))
    )
    (net (code "28") (name "28Vout4") (class "Default")
      (node (ref "R173") (pin "2") (pinfunction "2_2") (pintype "passive"))
      (node (ref "R98") (pin "2") (pinfunction "2_2") (pintype "passive"))
      (node (ref "U19") (pin "8") (pinfunction "RS-_8") (pintype "passive"))
    )
    (net (code "29") (name "GND") (class "Default")
      (node (ref "C100") (pin "1") (pinfunction "1_1") (pintype "passive"))
      (node (ref "C101") (pin "1") (pinfunction "1_1") (pintype "passive"))
      (node (ref "C103") (pin "1") (pinfunction "1_1") (pintype "passive"))
      (node (ref "C104") (pin "1") (pinfunction "1_1") (pintype "passive"))
      (node (ref "C105") (pin "1") (pinfunction "1_1") (pintype "passive"))
      (node (ref "C106") (pin "1") (pinfunction "1_1") (pintype "passive"))
      (node (ref "C114") (pin "1") (pinfunction "1_1") (pintype "passive"))
      (node (ref "C12") (pin "1") (pinfunction "1_1") (pintype "passive"))
      (node (ref "C121") (pin "1") (pinfunction "1_1") (pintype "passive"))
      (node (ref "C128") (pin "1") (pinfunction "1_1") (pintype "passive"))
      (node (ref "C129") (pin "1") (pinfunction "1_1") (pintype "passive"))
      (node (ref "C132") (pin "1") (pinfunction "1_1") (pintype "passive"))
      (node (ref "C133") (pin "1") (pinfunction "1_1") (pintype "passive"))
      (node (ref "C134") (pin "1") (pinfunction "1_1") (pintype "passive"))
      (node (ref "C135") (pin "1") (pinfunction "1_1") (pintype "passive"))
      (node (ref "C141") (pin "1") (pinfunction "1_1") (pintype "passive"))
      (node (ref "C142") (pin "1") (pinfunction "1_1") (pintype "passive"))
      (node (ref "C15") (pin "1") (pinfunction "1_1") (pintype "passive"))
      (node (ref "C18") (pin "2") (pinfunction "2_2") (pintype "passive"))
      (node (ref "C181") (pin "1") (pinfunction "1_1") (pintype "passive"))
      (node (ref "C182") (pin "1") (pinfunction "1_1") (pintype "passive"))
      (node (ref "C183") (pin "1") (pinfunction "1_1") (pintype "passive"))
      (node (ref "C185") (pin "1") (pinfunction "1_1") (pintype "passive"))
      (node (ref "C19") (pin "2") (pinfunction "2_2") (pintype "passive"))
      (node (ref "C22") (pin "1") (pinfunction "1_1") (pintype "passive"))
      (node (ref "C23") (pin "1") (pinfunction "1_1") (pintype "passive"))
      (node (ref "C43") (pin "1") (pinfunction "1_1") (pintype "passive"))
      (node (ref "C52") (pin "1") (pinfunction "1_1") (pintype "passive"))
      (node (ref "C61") (pin "1") (pinfunction "1_1") (pintype "passive"))
      (node (ref "C64") (pin "2") (pinfunction "2_2") (pintype "passive"))
      (node (ref "C65") (pin "1") (pinfunction "1_1") (pintype "passive"))
      (node (ref "C66") (pin "1") (pinfunction "1_1") (pintype "passive"))
      (node (ref "C67") (pin "1") (pinfunction "1_1") (pintype "passive"))
      (node (ref "C68") (pin "1") (pinfunction "1_1") (pintype "passive"))
      (node (ref "C69") (pin "1") (pinfunction "1_1") (pintype "passive"))
      (node (ref "C70") (pin "1") (pinfunction "1_1") (pintype "passive"))
      (node (ref "C72") (pin "2") (pinfunction "2_2") (pintype "passive"))
      (node (ref "C73") (pin "1") (pinfunction "1_1") (pintype "passive"))
      (node (ref "C74") (pin "1") (pinfunction "1_1") (pintype "passive"))
      (node (ref "C75") (pin "2") (pinfunction "2_2") (pintype "passive"))
      (node (ref "C76") (pin "1") (pinfunction "1_1") (pintype "passive"))
      (node (ref "C77") (pin "1") (pinfunction "1_1") (pintype "passive"))
      (node (ref "C78") (pin "1") (pinfunction "1_1") (pintype "passive"))
      (node (ref "C79") (pin "1") (pinfunction "1_1") (pintype "passive"))
      (node (ref "C80") (pin "1") (pinfunction "1_1") (pintype "passive"))
      (node (ref "C82") (pin "1") (pinfunction "1_1") (pintype "passive"))
      (node (ref "C84") (pin "1") (pinfunction "1_1") (pintype "passive"))
      (node (ref "C85") (pin "1") (pinfunction "1_1") (pintype "passive"))
      (node (ref "C86") (pin "1") (pinfunction "1_1") (pintype "passive"))
      (node (ref "C87") (pin "2") (pinfunction "2_2") (pintype "passive"))
      (node (ref "C88") (pin "1") (pinfunction "1_1") (pintype "passive"))
      (node (ref "C89") (pin "1") (pinfunction "1_1") (pintype "passive"))
      (node (ref "C91") (pin "2") (pinfunction "2_2") (pintype "passive"))
      (node (ref "C92") (pin "1") (pinfunction "1_1") (pintype "passive"))
      (node (ref "C93") (pin "1") (pinfunction "1_1") (pintype "passive"))
      (node (ref "C94") (pin "1") (pinfunction "1_1") (pintype "passive"))
      (node (ref "C95") (pin "1") (pinfunction "1_1") (pintype "passive"))
      (node (ref "D1") (pin "1") (pinfunction "A_1") (pintype "passive"))
      (node (ref "Q1") (pin "2") (pinfunction "E_2") (pintype "passive"))
      (node (ref "Q5") (pin "2") (pinfunction "E_2") (pintype "passive"))
      (node (ref "Q6") (pin "2") (pinfunction "E_2") (pintype "passive"))
      (node (ref "Q7") (pin "2") (pinfunction "E_2") (pintype "passive"))
      (node (ref "R103") (pin "1") (pinfunction "1_1") (pintype "passive"))
      (node (ref "R162") (pin "1") (pinfunction "1_1") (pintype "passive"))
      (node (ref "R165") (pin "1") (pinfunction "1_1") (pintype "passive"))
      (node (ref "R169") (pin "2") (pinfunction "2_2") (pintype "passive"))
      (node (ref "R184") (pin "1") (pinfunction "1_1") (pintype "passive"))
      (node (ref "R82") (pin "2") (pinfunction "2_2") (pintype "passive"))
      (node (ref "R86") (pin "1") (pinfunction "1_1") (pintype "passive"))
      (node (ref "U10") (pin "1") (pinfunction "GND_1") (pintype "passive"))
      (node (ref "U11") (pin "1") (pinfunction "GND_1") (pintype "passive"))
      (node (ref "U14") (pin "4") (pinfunction "GND_4") (pintype "passive"))
      (node (ref "U15") (pin "4") (pinfunction "GND_4") (pintype "passive"))
      (node (ref "U18") (pin "4") (pinfunction "GND_4") (pintype "passive"))
      (node (ref "U19") (pin "4") (pinfunction "GND_4") (pintype "passive"))
      (node (ref "U25") (pin "3") (pinfunction "GND_3") (pintype "passive"))
      (node (ref "U25") (pin "6") (pinfunction "GND_6") (pintype "passive"))
      (node (ref "U27") (pin "2") (pinfunction "GND_2") (pintype "passive"))
      (node (ref "U27") (pin "4") (pinfunction "GND_4") (pintype "passive"))
      (node (ref "U28") (pin "2") (pinfunction "GND_2") (pintype "passive"))
      (node (ref "U28") (pin "4") (pinfunction "GND_4") (pintype "passive"))
      (node (ref "U29") (pin "2") (pinfunction "GND_2") (pintype "passive"))
      (node (ref "U29") (pin "4") (pinfunction "GND_4") (pintype "passive"))
      (node (ref "U30") (pin "2") (pinfunction "GND_2") (pintype "passive"))
      (node (ref "U30") (pin "4") (pinfunction "GND_4") (pintype "passive"))
      (node (ref "U9") (pin "4") (pinfunction "ON/OFF_4") (pintype "passive"))
      (node (ref "U9") (pin "5") (pinfunction "GND_5") (pintype "passive"))
      (node (ref "U9") (pin "6") (pinfunction "GND_6") (pintype "passive"))
      (node (ref "U9") (pin "7") (pinfunction "GND_7") (pintype "passive"))
      (node (ref "U9") (pin "8") (pinfunction "GND_8") (pintype "passive"))
      (node (ref "U9") (pin "9") (pinfunction "EP-GND_9") (pintype "passive"))
    )
    (net (code "30") (name "Net-(C82-Pad2)") (class "Default")
      (node (ref "C82") (pin "2") (pinfunction "2_2") (pintype "passive"))
      (node (ref "R83") (pin "2") (pinfunction "2_2") (pintype "passive"))
      (node (ref "R84") (pin "2") (pinfunction "2_2") (pintype "passive"))
      (node (ref "R86") (pin "2") (pinfunction "2_2") (pintype "passive"))
    )
    (net (code "31") (name "Net-(D1-K)") (class "Default")
      (node (ref "D1") (pin "2") (pinfunction "K_2") (pintype "passive"))
      (node (ref "L4") (pin "1") (pinfunction "1_1") (pintype "passive"))
      (node (ref "U9") (pin "2") (pinfunction "VOUT_2") (pintype "passive"))
    )
    (net (code "32") (name "Net-(Q1-B)") (class "Default")
      (node (ref "Q1") (pin "1") (pinfunction "B_1") (pintype "passive"))
      (node (ref "R103") (pin "2") (pinfunction "2_2") (pintype "passive"))
      (node (ref "R95") (pin "2") (pinfunction "2_2") (pintype "passive"))
    )
    (net (code "33") (name "Net-(Q1-C)") (class "Default")
      (node (ref "Q1") (pin "3") (pinfunction "C_3") (pintype "passive"))
      (node (ref "R85") (pin "1") (pinfunction "1_1") (pintype "passive"))
      (node (ref "R88") (pin "1") (pinfunction "1_1") (pintype "passive"))
    )
    (net (code "34") (name "Net-(Q5-B)") (class "Default")
      (node (ref "Q5") (pin "1") (pinfunction "B_1") (pintype "passive"))
      (node (ref "R160") (pin "2") (pinfunction "2_2") (pintype "passive"))
      (node (ref "R162") (pin "2") (pinfunction "2_2") (pintype "passive"))
    )
    (net (code "35") (name "Net-(Q5-C)") (class "Default")
      (node (ref "Q5") (pin "3") (pinfunction "C_3") (pintype "passive"))
      (node (ref "R104") (pin "1") (pinfunction "1_1") (pintype "passive"))
      (node (ref "R107") (pin "1") (pinfunction "1_1") (pintype "passive"))
    )
    (net (code "36") (name "Net-(Q6-B)") (class "Default")
      (node (ref "Q6") (pin "1") (pinfunction "B_1") (pintype "passive"))
      (node (ref "R183") (pin "2") (pinfunction "2_2") (pintype "passive"))
      (node (ref "R184") (pin "2") (pinfunction "2_2") (pintype "passive"))
    )
    (net (code "37") (name "Net-(Q6-C)") (class "Default")
      (node (ref "Q6") (pin "3") (pinfunction "C_3") (pintype "passive"))
      (node (ref "R181") (pin "1") (pinfunction "1_1") (pintype "passive"))
      (node (ref "R87") (pin "1") (pinfunction "1_1") (pintype "passive"))
    )
    (net (code "38") (name "Net-(Q7-B)") (class "Default")
      (node (ref "Q7") (pin "1") (pinfunction "B_1") (pintype "passive"))
      (node (ref "R161") (pin "2") (pinfunction "2_2") (pintype "passive"))
      (node (ref "R165") (pin "2") (pinfunction "2_2") (pintype "passive"))
    )
    (net (code "39") (name "Net-(Q7-C)") (class "Default")
      (node (ref "Q7") (pin "3") (pinfunction "C_3") (pintype "passive"))
      (node (ref "R105") (pin "1") (pinfunction "1_1") (pintype "passive"))
      (node (ref "R123") (pin "1") (pinfunction "1_1") (pintype "passive"))
    )
    (net (code "40") (name "Net-(R166-Pad2)") (class "Default")
      (node (ref "R166") (pin "2") (pinfunction "2_2") (pintype "passive"))
      (node (ref "R80") (pin "1") (pinfunction "1_1") (pintype "passive"))
    )
    (net (code "41") (name "Net-(R167-Pad1)") (class "Default")
      (node (ref "R167") (pin "1") (pinfunction "1_1") (pintype "passive"))
      (node (ref "R168") (pin "2") (pinfunction "2_2") (pintype "passive"))
    )
    (net (code "42") (name "Net-(U4-G)") (class "Default")
      (node (ref "R87") (pin "2") (pinfunction "2_2") (pintype "passive"))
      (node (ref "U4") (pin "1") (pinfunction "G_1") (pintype "passive"))
    )
    (net (code "43") (name "Net-(U4-S)") (class "Default")
      (node (ref "C141") (pin "2") (pinfunction "2_2") (pintype "passive"))
      (node (ref "C18") (pin "1") (pinfunction "1_1") (pintype "passive"))
      (node (ref "FB18") (pin "1") (pinfunction "1_1") (pintype "passive"))
      (node (ref "U4") (pin "2") (pinfunction "S_2") (pintype "passive"))
    )
    (net (code "44") (name "Net-(U9-FB{slash}ADJ)") (class "Default")
      (node (ref "R166") (pin "1") (pinfunction "1_1") (pintype "passive"))
      (node (ref "R82") (pin "1") (pinfunction "1_1") (pintype "passive"))
      (node (ref "U9") (pin "3") (pinfunction "FB/ADJ_3") (pintype "passive"))
    )
    (net (code "45") (name "Net-(U12-G)") (class "Default")
      (node (ref "R88") (pin "2") (pinfunction "2_2") (pintype "passive"))
      (node (ref "U12") (pin "1") (pinfunction "G_1") (pintype "passive"))
    )
    (net (code "46") (name "Net-(U12-S)") (class "Default")
      (node (ref "C15") (pin "2") (pinfunction "2_2") (pintype "passive"))
      (node (ref "C19") (pin "1") (pinfunction "1_1") (pintype "passive"))
      (node (ref "FB15") (pin "1") (pinfunction "1_1") (pintype "passive"))
      (node (ref "U12") (pin "2") (pinfunction "S_2") (pintype "passive"))
    )
    (net (code "47") (name "Net-(U14-OUT)") (class "Default")
      (node (ref "R93") (pin "1") (pinfunction "1_1") (pintype "passive"))
      (node (ref "U14") (pin "5") (pinfunction "OUT_5") (pintype "passive"))
    )
    (net (code "48") (name "Net-(U15-OUT)") (class "Default")
      (node (ref "R94") (pin "1") (pinfunction "1_1") (pintype "passive"))
      (node (ref "U15") (pin "5") (pinfunction "OUT_5") (pintype "passive"))
    )
    (net (code "49") (name "Net-(U18-OUT)") (class "Default")
      (node (ref "R100") (pin "1") (pinfunction "1_1") (pintype "passive"))
      (node (ref "U18") (pin "5") (pinfunction "OUT_5") (pintype "passive"))
    )
    (net (code "50") (name "Net-(U19-OUT)") (class "Default")
      (node (ref "R101") (pin "1") (pinfunction "1_1") (pintype "passive"))
      (node (ref "U19") (pin "5") (pinfunction "OUT_5") (pintype "passive"))
    )
    (net (code "51") (name "Net-(U20-G)") (class "Default")
      (node (ref "R107") (pin "2") (pinfunction "2_2") (pintype "passive"))
      (node (ref "U20") (pin "1") (pinfunction "G_1") (pintype "passive"))
    )
    (net (code "52") (name "Net-(U20-S)") (class "Default")
      (node (ref "C61") (pin "2") (pinfunction "2_2") (pintype "passive"))
      (node (ref "C75") (pin "1") (pinfunction "1_1") (pintype "passive"))
      (node (ref "FB16") (pin "1") (pinfunction "1_1") (pintype "passive"))
      (node (ref "U20") (pin "2") (pinfunction "S_2") (pintype "passive"))
    )
    (net (code "53") (name "Net-(U21-G)") (class "Default")
      (node (ref "R123") (pin "2") (pinfunction "2_2") (pintype "passive"))
      (node (ref "U21") (pin "1") (pinfunction "G_1") (pintype "passive"))
    )
    (net (code "54") (name "Net-(U21-S)") (class "Default")
      (node (ref "C74") (pin "2") (pinfunction "2_2") (pintype "passive"))
      (node (ref "C91") (pin "1") (pinfunction "1_1") (pintype "passive"))
      (node (ref "FB17") (pin "1") (pinfunction "1_1") (pintype "passive"))
      (node (ref "U21") (pin "2") (pinfunction "S_2") (pintype "passive"))
    )
    (net (code "55") (name "Net-(U25-EN)") (class "Default")
      (node (ref "R231") (pin "1") (pinfunction "1_1") (pintype "passive"))
      (node (ref "U25") (pin "5") (pinfunction "EN_5") (pintype "passive"))
    )
    (net (code "56") (name "Net-(U25-NR{slash}FB)") (class "Default")
      (node (ref "C184") (pin "1") (pinfunction "1_1") (pintype "passive"))
      (node (ref "R168") (pin "1") (pinfunction "1_1") (pintype "passive"))
      (node (ref "R169") (pin "1") (pinfunction "1_1") (pintype "passive"))
      (node (ref "U25") (pin "4") (pinfunction "NR/FB_4") (pintype "passive"))
    )
    (net (code "57") (name "unconnected-(U14-NC-Pad3)") (class "Default")
      (node (ref "U14") (pin "3") (pinfunction "NC_3") (pintype "passive"))
    )
    (net (code "58") (name "unconnected-(U14-NC-Pad6)") (class "Default")
      (node (ref "U14") (pin "6") (pinfunction "NC_6") (pintype "passive"))
    )
    (net (code "59") (name "unconnected-(U14-NC-Pad7)") (class "Default")
      (node (ref "U14") (pin "7") (pinfunction "NC_7") (pintype "passive"))
    )
    (net (code "60") (name "unconnected-(U15-NC-Pad3)") (class "Default")
      (node (ref "U15") (pin "3") (pinfunction "NC_3") (pintype "passive"))
    )
    (net (code "61") (name "unconnected-(U15-NC-Pad6)") (class "Default")
      (node (ref "U15") (pin "6") (pinfunction "NC_6") (pintype "passive"))
    )
    (net (code "62") (name "unconnected-(U15-NC-Pad7)") (class "Default")
      (node (ref "U15") (pin "7") (pinfunction "NC_7") (pintype "passive"))
    )
    (net (code "63") (name "unconnected-(U18-NC-Pad3)") (class "Default")
      (node (ref "U18") (pin "3") (pinfunction "NC_3") (pintype "passive"))
    )
    (net (code "64") (name "unconnected-(U18-NC-Pad6)") (class "Default")
      (node (ref "U18") (pin "6") (pinfunction "NC_6") (pintype "passive"))
    )
    (net (code "65") (name "unconnected-(U18-NC-Pad7)") (class "Default")
      (node (ref "U18") (pin "7") (pinfunction "NC_7") (pintype "passive"))
    )
    (net (code "66") (name "unconnected-(U19-NC-Pad3)") (class "Default")
      (node (ref "U19") (pin "3") (pinfunction "NC_3") (pintype "passive"))
    )
    (net (code "67") (name "unconnected-(U19-NC-Pad6)") (class "Default")
      (node (ref "U19") (pin "6") (pinfunction "NC_6") (pintype "passive"))
    )
    (net (code "68") (name "unconnected-(U19-NC-Pad7)") (class "Default")
      (node (ref "U19") (pin "7") (pinfunction "NC_7") (pintype "passive"))
    )
  )
)
